# preamp.net
KiCad netlist of a schematic drawn in EAGLE
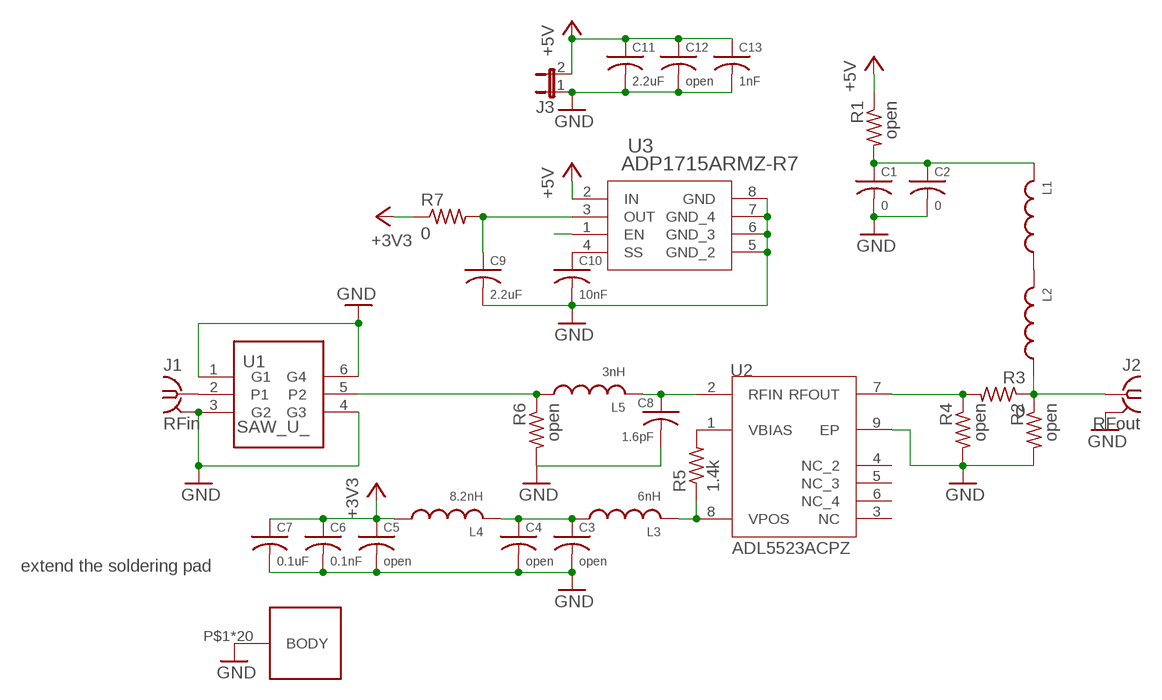
[diagram p0: schematic, sheet 1]

(export (version "E")
  (design (tool "Eeschema 10.0.6"))
  (components
    (comp (ref "C1")
      (value "0")
      (footprint "eagle-import:C0603")
      (libsource (lib "eagle-import") (part "C-USC0603"))
    )
    (comp (ref "C2")
      (value "0")
      (footprint "eagle-import:C0603")
      (libsource (lib "eagle-import") (part "C-USC0603"))
    )
    (comp (ref "C3")
      (value "open")
      (footprint "eagle-import:C0603")
      (libsource (lib "eagle-import") (part "C-USC0603"))
    )
    (comp (ref "C4")
      (value "open")
      (footprint "eagle-import:C0603")
      (libsource (lib "eagle-import") (part "C-USC0603"))
    )
    (comp (ref "C5")
      (value "open")
      (footprint "eagle-import:C0603")
      (libsource (lib "eagle-import") (part "C-USC0603"))
    )
    (comp (ref "C6")
      (value "0.1nF")
      (footprint "eagle-import:C0603")
      (libsource (lib "eagle-import") (part "C-USC0603"))
    )
    (comp (ref "C7")
      (value "0.1uF")
      (footprint "eagle-import:C0603")
      (libsource (lib "eagle-import") (part "C-USC0603"))
    )
    (comp (ref "C8")
      (value "1.6pF")
      (footprint "eagle-import:C0603")
      (libsource (lib "eagle-import") (part "C-USC0603"))
    )
    (comp (ref "C9")
      (value "2.2uF")
      (footprint "eagle-import:C0603")
      (libsource (lib "eagle-import") (part "C-USC0603"))
    )
    (comp (ref "C10")
      (value "10nF")
      (footprint "eagle-import:C0603")
      (libsource (lib "eagle-import") (part "C-USC0603"))
    )
    (comp (ref "C11")
      (value "2.2uF")
      (footprint "eagle-import:C0603")
      (libsource (lib "eagle-import") (part "C-USC0603"))
    )
    (comp (ref "C12")
      (value "open")
      (footprint "eagle-import:C0603")
      (libsource (lib "eagle-import") (part "C-USC0603"))
    )
    (comp (ref "C13")
      (value "1nF")
      (footprint "eagle-import:C0603")
      (libsource (lib "eagle-import") (part "C-USC0603"))
    )
    (comp (ref "J1")
      (value "RFin")
      (footprint "eagle-import:J502-ND-142-0711-821_826")
      (fields
        (field (name "MF") "JOHNSON COMPONENTS")
        (field (name "MPN") "142-0711-821")
        (field (name "MPN_1") "142-0711-821")
        (field (name "OC_FARNELL") "1019328")
        (field (name "OC_NEWARK") "16F3627")
      )
      (libsource (lib "eagle-import") (part "SMA-142-0711-821/826"))
    )
    (comp (ref "J2")
      (value "RFout")
      (footprint "eagle-import:J502-ND-142-0711-821_826")
      (fields
        (field (name "MF") "JOHNSON COMPONENTS")
        (field (name "MPN") "142-0711-821")
        (field (name "MF_1") "JOHNSON COMPONENTS")
        (field (name "MPN_1") "142-0711-821")
        (field (name "OC_FARNELL") "1019328")
        (field (name "OC_NEWARK") "16F3627")
      )
      (libsource (lib "eagle-import") (part "SMA-142-0711-821/826"))
    )
    (comp (ref "J3")
      (value "JP1E")
      (footprint "eagle-import:JP1")
      (libsource (lib "eagle-import") (part "JP1E"))
    )
    (comp (ref "L1")
      (value "L-USL0603")
      (footprint "eagle-import:L0603")
      (libsource (lib "eagle-import") (part "L-USL0603"))
    )
    (comp (ref "L2")
      (value "L-USL0603")
      (footprint "eagle-import:L0603")
      (libsource (lib "eagle-import") (part "L-USL0603"))
    )
    (comp (ref "L3")
      (value "6nH")
      (footprint "eagle-import:L0603")
      (libsource (lib "eagle-import") (part "L-USL0603"))
    )
    (comp (ref "L4")
      (value "8.2nH")
      (footprint "eagle-import:L0603")
      (libsource (lib "eagle-import") (part "L-USL0603"))
    )
    (comp (ref "L5")
      (value "3nH")
      (footprint "eagle-import:L0603")
      (libsource (lib "eagle-import") (part "L-USL0603"))
    )
    (comp (ref "R1")
      (value "open")
      (footprint "eagle-import:R0603")
      (libsource (lib "eagle-import") (part "R-US_R0603"))
    )
    (comp (ref "R2")
      (value "open")
      (footprint "eagle-import:R0603")
      (libsource (lib "eagle-import") (part "R-US_R0603"))
    )
    (comp (ref "R3")
      (value "0")
      (footprint "eagle-import:R0603")
      (libsource (lib "eagle-import") (part "R-US_R0603"))
    )
    (comp (ref "R4")
      (value "open")
      (footprint "eagle-import:R0603")
      (libsource (lib "eagle-import") (part "R-US_R0603"))
    )
    (comp (ref "R5")
      (value "1.4k")
      (footprint "eagle-import:R0603")
      (libsource (lib "eagle-import") (part "R-US_R0603"))
    )
    (comp (ref "R6")
      (value "open")
      (footprint "eagle-import:R0603")
      (libsource (lib "eagle-import") (part "R-US_R0603"))
    )
    (comp (ref "R7")
      (value "0")
      (footprint "eagle-import:R0603")
      (libsource (lib "eagle-import") (part "R-US_R0603"))
    )
    (comp (ref "U1")
      (value "SAW_U_")
      (footprint "eagle-import:SAW_U")
      (libsource (lib "eagle-import") (part "SAW_U_"))
    )
    (comp (ref "U2")
      (value "ADL5523ACPZ")
      (footprint "eagle-import:CP8-2_DZ")
      (libsource (lib "eagle-import") (part "ADL5523ACPZ"))
    )
    (comp (ref "U3")
      (value "ADP1715ARMZ-R7")
      (footprint "eagle-import:RM_8")
      (libsource (lib "eagle-import") (part "ADP1715ARMZ-R7"))
    )
    (comp (ref "U10")
      (value "BMI-S-X03")
      (footprint "eagle-import:BMI-S-X03")
      (libsource (lib "eagle-import") (part "BMI-S-X03"))
    )
  )
  (nets
    (net (code "1") (name "+3V3") (class "Default")
      (node (ref "C5") (pin "1") (pinfunction "1_1") (pintype "passive"))
      (node (ref "C6") (pin "1") (pinfunction "1_1") (pintype "passive"))
      (node (ref "C7") (pin "1") (pinfunction "1_1") (pintype "passive"))
      (node (ref "L4") (pin "1") (pinfunction "1_1") (pintype "passive"))
      (node (ref "R7") (pin "1") (pinfunction "1_1") (pintype "passive"))
    )
    (net (code "2") (name "+5V") (class "Default")
      (node (ref "C11") (pin "1") (pinfunction "1_1") (pintype "passive"))
      (node (ref "C12") (pin "1") (pinfunction "1_1") (pintype "passive"))
      (node (ref "C13") (pin "1") (pinfunction "1_1") (pintype "passive"))
      (node (ref "J3") (pin "2") (pinfunction "2_2") (pintype "passive"))
      (node (ref "R1") (pin "1") (pinfunction "1_1") (pintype "passive"))
      (node (ref "U3") (pin "1") (pinfunction "EN_1") (pintype "passive"))
      (node (ref "U3") (pin "2") (pinfunction "IN_2") (pintype "passive"))
    )
    (net (code "3") (name "GND") (class "Default")
      (node (ref "C1") (pin "2") (pinfunction "2_2") (pintype "passive"))
      (node (ref "C10") (pin "2") (pinfunction "2_2") (pintype "passive"))
      (node (ref "C11") (pin "2") (pinfunction "2_2") (pintype "passive"))
      (node (ref "C12") (pin "2") (pinfunction "2_2") (pintype "passive"))
      (node (ref "C13") (pin "2") (pinfunction "2_2") (pintype "passive"))
      (node (ref "C2") (pin "2") (pinfunction "2_2") (pintype "passive"))
      (node (ref "C3") (pin "2") (pinfunction "2_2") (pintype "passive"))
      (node (ref "C4") (pin "2") (pinfunction "2_2") (pintype "passive"))
      (node (ref "C5") (pin "2") (pinfunction "2_2") (pintype "passive"))
      (node (ref "C6") (pin "2") (pinfunction "2_2") (pintype "passive"))
      (node (ref "C7") (pin "2") (pinfunction "2_2") (pintype "passive"))
      (node (ref "C8") (pin "2") (pinfunction "2_2") (pintype "passive"))
      (node (ref "C9") (pin "2") (pinfunction "2_2") (pintype "passive"))
      (node (ref "J1") (pin "G@1") (pinfunction "GND_G@1") (pintype "power_in"))
      (node (ref "J2") (pin "G@1") (pinfunction "GND_G@1") (pintype "power_in"))
      (node (ref "J3") (pin "1") (pinfunction "1_1") (pintype "passive"))
      (node (ref "R2") (pin "2") (pinfunction "2_2") (pintype "passive"))
      (node (ref "R4") (pin "2") (pinfunction "2_2") (pintype "passive"))
      (node (ref "R6") (pin "2") (pinfunction "2_2") (pintype "passive"))
      (node (ref "U1") (pin "1") (pinfunction "G1_1") (pintype "bidirectional"))
      (node (ref "U1") (pin "3") (pinfunction "G2_3") (pintype "bidirectional"))
      (node (ref "U1") (pin "4") (pinfunction "G3_4") (pintype "bidirectional"))
      (node (ref "U1") (pin "6") (pinfunction "G4_6") (pintype "bidirectional"))
      (node (ref "U10") (pin "P$1") (pinfunction "BODY_P$1") (pintype "bidirectional"))
      (node (ref "U10") (pin "P$10") (pinfunction "BODY_P$10") (pintype "bidirectional"))
      (node (ref "U10") (pin "P$11") (pinfunction "BODY_P$11") (pintype "bidirectional"))
      (node (ref "U10") (pin "P$12") (pinfunction "BODY_P$12") (pintype "bidirectional"))
      (node (ref "U10") (pin "P$13") (pinfunction "BODY_P$13") (pintype "bidirectional"))
      (node (ref "U10") (pin "P$14") (pinfunction "BODY_P$14") (pintype "bidirectional"))
      (node (ref "U10") (pin "P$15") (pinfunction "BODY_P$15") (pintype "bidirectional"))
      (node (ref "U10") (pin "P$16") (pinfunction "BODY_P$16") (pintype "bidirectional"))
      (node (ref "U10") (pin "P$17") (pinfunction "BODY_P$17") (pintype "bidirectional"))
      (node (ref "U10") (pin "P$18") (pinfunction "BODY_P$18") (pintype "bidirectional"))
      (node (ref "U10") (pin "P$19") (pinfunction "BODY_P$19") (pintype "bidirectional"))
      (node (ref "U10") (pin "P$2") (pinfunction "BODY_P$2") (pintype "bidirectional"))
      (node (ref "U10") (pin "P$20") (pinfunction "BODY_P$20") (pintype "bidirectional"))
      (node (ref "U10") (pin "P$21") (pinfunction "BODY_P$21") (pintype "bidirectional"))
      (node (ref "U10") (pin "P$3") (pinfunction "BODY_P$3") (pintype "bidirectional"))
      (node (ref "U10") (pin "P$4") (pinfunction "BODY_P$4") (pintype "bidirectional"))
      (node (ref "U10") (pin "P$5") (pinfunction "BODY_P$5") (pintype "bidirectional"))
      (node (ref "U10") (pin "P$6") (pinfunction "BODY_P$6") (pintype "bidirectional"))
      (node (ref "U10") (pin "P$7") (pinfunction "BODY_P$7") (pintype "bidirectional"))
      (node (ref "U10") (pin "P$8") (pinfunction "BODY_P$8") (pintype "bidirectional"))
      (node (ref "U2") (pin "9") (pinfunction "EP_9") (pintype "passive"))
      (node (ref "U3") (pin "5") (pinfunction "GND_2_5") (pintype "passive"))
      (node (ref "U3") (pin "6") (pinfunction "GND_3_6") (pintype "passive"))
      (node (ref "U3") (pin "7") (pinfunction "GND_4_7") (pintype "passive"))
      (node (ref "U3") (pin "8") (pinfunction "GND_8") (pintype "passive"))
    )
    (net (code "4") (name "Net-(C1-Pad1)") (class "Default")
      (node (ref "C1") (pin "1") (pinfunction "1_1") (pintype "passive"))
      (node (ref "C2") (pin "1") (pinfunction "1_1") (pintype "passive"))
      (node (ref "L1") (pin "2") (pinfunction "2_2") (pintype "passive"))
      (node (ref "R1") (pin "2") (pinfunction "2_2") (pintype "passive"))
    )
    (net (code "5") (name "Net-(C3-Pad1)") (class "Default")
      (node (ref "C3") (pin "1") (pinfunction "1_1") (pintype "passive"))
      (node (ref "C4") (pin "1") (pinfunction "1_1") (pintype "passive"))
      (node (ref "L3") (pin "1") (pinfunction "1_1") (pintype "passive"))
      (node (ref "L4") (pin "2") (pinfunction "2_2") (pintype "passive"))
    )
    (net (code "6") (name "Net-(J2-Pad1)") (class "Default")
      (node (ref "J2") (pin "1") (pinfunction "1_1") (pintype "passive"))
      (node (ref "L2") (pin "1") (pinfunction "1_1") (pintype "passive"))
      (node (ref "R2") (pin "1") (pinfunction "1_1") (pintype "passive"))
      (node (ref "R3") (pin "1") (pinfunction "1_1") (pintype "passive"))
    )
    (net (code "7") (name "Net-(L1-Pad1)") (class "Default")
      (node (ref "L1") (pin "1") (pinfunction "1_1") (pintype "passive"))
      (node (ref "L2") (pin "2") (pinfunction "2_2") (pintype "passive"))
    )
    (net (code "8") (name "Net-(U1-P1)") (class "Default")
      (node (ref "J1") (pin "1") (pinfunction "1_1") (pintype "passive"))
      (node (ref "U1") (pin "2") (pinfunction "P1_2") (pintype "bidirectional"))
    )
    (net (code "9") (name "Net-(U1-P2)") (class "Default")
      (node (ref "L5") (pin "1") (pinfunction "1_1") (pintype "passive"))
      (node (ref "R6") (pin "1") (pinfunction "1_1") (pintype "passive"))
      (node (ref "U1") (pin "5") (pinfunction "P2_5") (pintype "bidirectional"))
    )
    (net (code "10") (name "Net-(U2-RFIN)") (class "Default")
      (node (ref "C8") (pin "1") (pinfunction "1_1") (pintype "passive"))
      (node (ref "L5") (pin "2") (pinfunction "2_2") (pintype "passive"))
      (node (ref "U2") (pin "2") (pinfunction "RFIN_2") (pintype "passive"))
    )
    (net (code "11") (name "Net-(U2-RFOUT)") (class "Default")
      (node (ref "R3") (pin "2") (pinfunction "2_2") (pintype "passive"))
      (node (ref "R4") (pin "1") (pinfunction "1_1") (pintype "passive"))
      (node (ref "U2") (pin "7") (pinfunction "RFOUT_7") (pintype "passive"))
    )
    (net (code "12") (name "Net-(U2-VBIAS)") (class "Default")
      (node (ref "R5") (pin "2") (pinfunction "2_2") (pintype "passive"))
      (node (ref "U2") (pin "1") (pinfunction "VBIAS_1") (pintype "passive"))
    )
    (net (code "13") (name "Net-(U2-VPOS)") (class "Default")
      (node (ref "L3") (pin "2") (pinfunction "2_2") (pintype "passive"))
      (node (ref "R5") (pin "1") (pinfunction "1_1") (pintype "passive"))
      (node (ref "U2") (pin "8") (pinfunction "VPOS_8") (pintype "power_in"))
    )
    (net (code "14") (name "Net-(U3-OUT)") (class "Default")
      (node (ref "C9") (pin "1") (pinfunction "1_1") (pintype "passive"))
      (node (ref "R7") (pin "2") (pinfunction "2_2") (pintype "passive"))
      (node (ref "U3") (pin "3") (pinfunction "OUT_3") (pintype "passive"))
    )
    (net (code "15") (name "Net-(U3-SS)") (class "Default")
      (node (ref "C10") (pin "1") (pinfunction "1_1") (pintype "passive"))
      (node (ref "U3") (pin "4") (pinfunction "SS_4") (pintype "passive"))
    )
    (net (code "16") (name "unconnected-(U2-NC-Pad3)") (class "Default")
      (node (ref "U2") (pin "3") (pinfunction "NC_3") (pintype "passive"))
    )
    (net (code "17") (name "unconnected-(U2-NC_2-Pad4)") (class "Default")
      (node (ref "U2") (pin "4") (pinfunction "NC_2_4") (pintype "passive"))
    )
    (net (code "18") (name "unconnected-(U2-NC_3-Pad5)") (class "Default")
      (node (ref "U2") (pin "5") (pinfunction "NC_3_5") (pintype "passive"))
    )
    (net (code "19") (name "unconnected-(U2-NC_4-Pad6)") (class "Default")
      (node (ref "U2") (pin "6") (pinfunction "NC_4_6") (pintype "passive"))
    )
  )
)
